# generator3.net
KiCad netlist of a schematic drawn in EAGLE
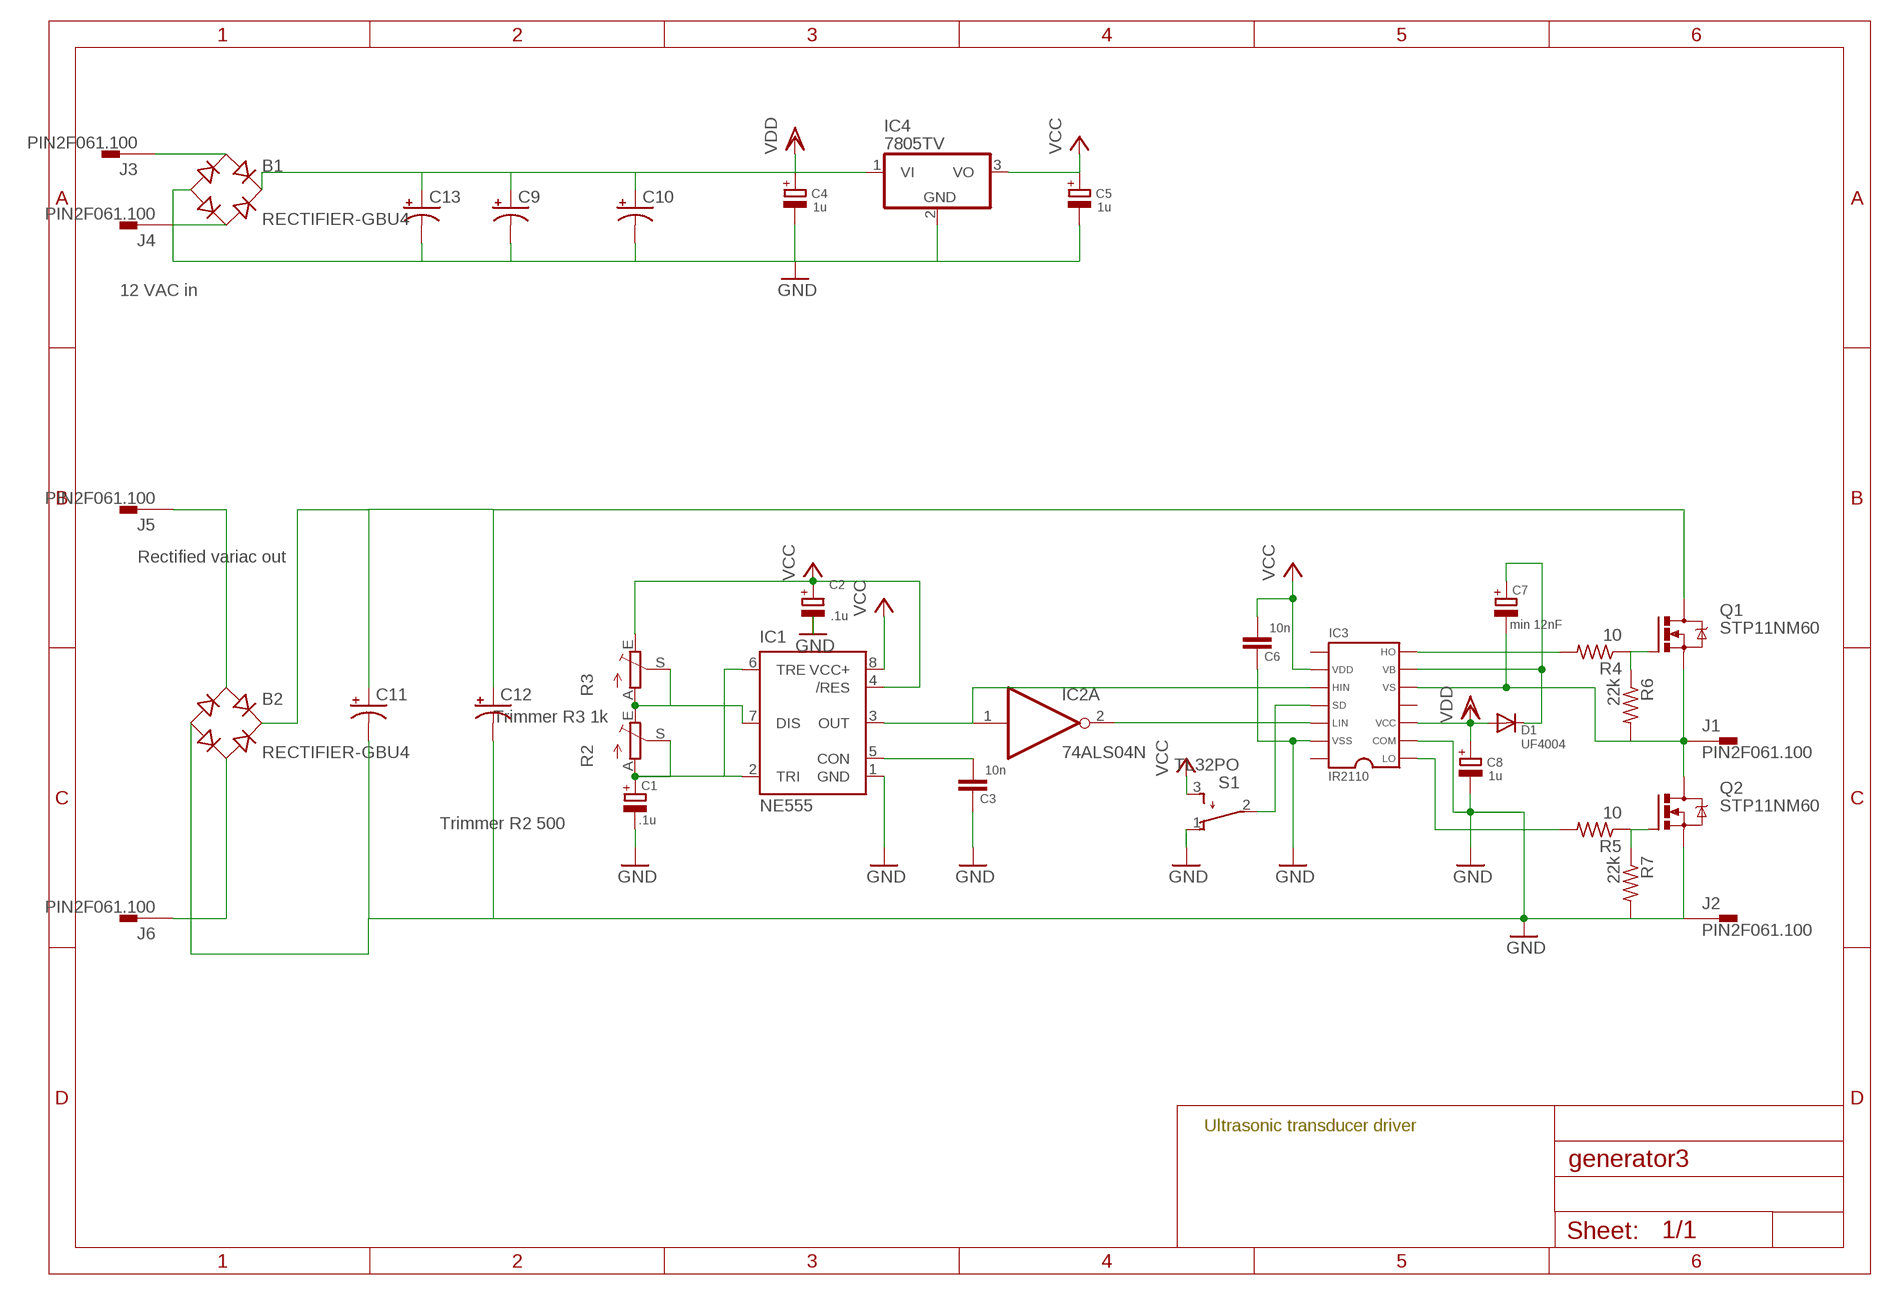
[diagram p0: schematic, sheet 1]

(export (version "E")
  (design (tool "Eeschema 10.0.6"))
  (components
    (comp (ref "B1")
      (value "RECTIFIER-GBU4")
      (footprint "eagle-import:GBU4")
      (libsource (lib "eagle-import") (part "RECTIFIER-GBU4"))
    )
    (comp (ref "B2")
      (value "RECTIFIER-GBU4")
      (footprint "eagle-import:GBU4")
      (libsource (lib "eagle-import") (part "RECTIFIER-GBU4"))
    )
    (comp (ref "C1")
      (value ".1u")
      (footprint "eagle-import:E5-8,5")
      (libsource (lib "eagle-import") (part "CPOL-EUE5-8.5"))
    )
    (comp (ref "C2")
      (value ".1u")
      (footprint "eagle-import:E5-8,5")
      (libsource (lib "eagle-import") (part "CPOL-EUE5-8.5"))
    )
    (comp (ref "C3")
      (value "10n")
      (footprint "eagle-import:C075-052X106")
      (libsource (lib "eagle-import") (part "C-EU075-052X106"))
    )
    (comp (ref "C4")
      (value "1u")
      (footprint "eagle-import:E5-8,5")
      (libsource (lib "eagle-import") (part "CPOL-EUE5-8.5"))
    )
    (comp (ref "C5")
      (value "1u")
      (footprint "eagle-import:E5-8,5")
      (libsource (lib "eagle-import") (part "CPOL-EUE5-8.5"))
    )
    (comp (ref "C6")
      (value "10n")
      (footprint "eagle-import:C075-052X106")
      (libsource (lib "eagle-import") (part "C-EU075-052X106"))
    )
    (comp (ref "C7")
      (value "min 12nF")
      (footprint "eagle-import:E5-8,5")
      (libsource (lib "eagle-import") (part "CPOL-EUE5-8.5"))
    )
    (comp (ref "C8")
      (value "1u")
      (footprint "eagle-import:E5-8,5")
      (libsource (lib "eagle-import") (part "CPOL-EUE5-8.5"))
    )
    (comp (ref "C9")
      (value "CPOL-USE7.5-18")
      (footprint "eagle-import:E7,5-18")
      (libsource (lib "eagle-import") (part "CPOL-USE7.5-18"))
    )
    (comp (ref "C10")
      (value "CPOL-USE7.5-18")
      (footprint "eagle-import:E7,5-18")
      (libsource (lib "eagle-import") (part "CPOL-USE7.5-18"))
    )
    (comp (ref "C11")
      (value "CPOL-USE10-35")
      (footprint "eagle-import:EB35D")
      (libsource (lib "eagle-import") (part "CPOL-USE10-35"))
    )
    (comp (ref "C12")
      (value "CPOL-USE10-35")
      (footprint "eagle-import:EB35D")
      (libsource (lib "eagle-import") (part "CPOL-USE10-35"))
    )
    (comp (ref "C13")
      (value "CPOL-USE7.5-18")
      (footprint "eagle-import:E7,5-18")
      (libsource (lib "eagle-import") (part "CPOL-USE7.5-18"))
    )
    (comp (ref "D1")
      (value "UF4004")
      (footprint "eagle-import:D-7.5")
      (libsource (lib "eagle-import") (part "DIODE-D-7.5"))
    )
    (comp (ref "IC1")
      (value "NE555")
      (footprint "eagle-import:DIL-08")
      (fields (field (name "MF") "Arrow Electronics") (field (name "MPN") "NE555N"))
      (libsource (lib "eagle-import") (part "NE555"))
    )
    (comp (ref "IC2")
      (value "74ALS04N")
      (footprint "eagle-import:DIL14")
      (libsource (lib "eagle-import") (part "7404NALS"))
    )
    (comp (ref "IC3")
      (value "IR2110")
      (footprint "eagle-import:DIL14")
      (libsource (lib "eagle-import") (part "IR2110"))
    )
    (comp (ref "IC4")
      (value "7805TV")
      (footprint "eagle-import:TO220V")
      (libsource (lib "eagle-import") (part "78TV05"))
    )
    (comp (ref "J1")
      (value "PIN2F061.100")
      (footprint "eagle-import:F061.100")
      (libsource (lib "eagle-import") (part "PIN2F061.100"))
    )
    (comp (ref "J2")
      (value "PIN2F061.100")
      (footprint "eagle-import:F061.100")
      (libsource (lib "eagle-import") (part "PIN2F061.100"))
    )
    (comp (ref "J3")
      (value "PIN2F061.100")
      (footprint "eagle-import:F061.100")
      (libsource (lib "eagle-import") (part "PIN2F061.100"))
    )
    (comp (ref "J4")
      (value "PIN2F061.100")
      (footprint "eagle-import:F061.100")
      (libsource (lib "eagle-import") (part "PIN2F061.100"))
    )
    (comp (ref "J5")
      (value "PIN2F061.100")
      (footprint "eagle-import:F061.100")
      (libsource (lib "eagle-import") (part "PIN2F061.100"))
    )
    (comp (ref "J6")
      (value "PIN2F061.100")
      (footprint "eagle-import:F061.100")
      (libsource (lib "eagle-import") (part "PIN2F061.100"))
    )
    (comp (ref "Q1")
      (value "STP11NM60")
      (footprint "eagle-import:TO220BV")
      (libsource (lib "eagle-import") (part "IRF530"))
    )
    (comp (ref "Q2")
      (value "STP11NM60")
      (footprint "eagle-import:TO220BV")
      (libsource (lib "eagle-import") (part "IRF530"))
    )
    (comp (ref "R2")
      (value "TRIM_EU-LI10")
      (footprint "eagle-import:LI10")
      (libsource (lib "eagle-import") (part "TRIM_EU-LI10"))
    )
    (comp (ref "R3")
      (value "TRIM_EU-LI10")
      (footprint "eagle-import:LI10")
      (libsource (lib "eagle-import") (part "TRIM_EU-LI10"))
    )
    (comp (ref "R4")
      (value "10")
      (footprint "eagle-import:0207_10")
      (libsource (lib "eagle-import") (part "R-US_0207/10"))
    )
    (comp (ref "R5")
      (value "10")
      (footprint "eagle-import:0207_10")
      (libsource (lib "eagle-import") (part "R-US_0207/10"))
    )
    (comp (ref "R6")
      (value "22k")
      (footprint "eagle-import:0207_10")
      (libsource (lib "eagle-import") (part "R-US_0207/10"))
    )
    (comp (ref "R7")
      (value "22k")
      (footprint "eagle-import:0207_10")
      (libsource (lib "eagle-import") (part "R-US_0207/10"))
    )
    (comp (ref "S1")
      (value "TL32PO")
      (footprint "eagle-import:TL3XPO")
      (libsource (lib "eagle-import") (part "TL32PO"))
    )
  )
  (nets
    (net (code "1") (name "GND") (class "Default")
      (node (ref "B1") (pin "-") (pinfunction "-_-") (pintype "passive"))
      (node (ref "B2") (pin "-") (pinfunction "-_-") (pintype "passive"))
      (node (ref "C1") (pin "-") (pinfunction "-_-") (pintype "passive"))
      (node (ref "C10") (pin "-") (pinfunction "-_-") (pintype "passive"))
      (node (ref "C11") (pin "-") (pinfunction "-_-") (pintype "passive"))
      (node (ref "C12") (pin "-") (pinfunction "-_-") (pintype "passive"))
      (node (ref "C13") (pin "-") (pinfunction "-_-") (pintype "passive"))
      (node (ref "C2") (pin "-") (pinfunction "-_-") (pintype "passive"))
      (node (ref "C3") (pin "1") (pinfunction "1_1") (pintype "passive"))
      (node (ref "C4") (pin "-") (pinfunction "-_-") (pintype "passive"))
      (node (ref "C5") (pin "-") (pinfunction "-_-") (pintype "passive"))
      (node (ref "C6") (pin "1") (pinfunction "1_1") (pintype "passive"))
      (node (ref "C8") (pin "-") (pinfunction "-_-") (pintype "passive"))
      (node (ref "C9") (pin "-") (pinfunction "-_-") (pintype "passive"))
      (node (ref "IC1") (pin "1") (pinfunction "GND_1") (pintype "power_in"))
      (node (ref "IC3") (pin "13") (pinfunction "13_13") (pintype "passive"))
      (node (ref "IC3") (pin "2") (pinfunction "2_2") (pintype "passive"))
      (node (ref "IC4") (pin "2") (pinfunction "GND_2") (pintype "passive"))
      (node (ref "J2") (pin "A1") (pinfunction "1_A1") (pintype "passive"))
      (node (ref "J2") (pin "A2") (pinfunction "1_A2") (pintype "passive"))
      (node (ref "Q2") (pin "S") (pinfunction "S_S") (pintype "passive"))
      (node (ref "R7") (pin "2") (pinfunction "2_2") (pintype "passive"))
      (node (ref "S1") (pin "1") (pinfunction "O_1") (pintype "passive"))
    )
    (net (code "2") (name "Net-(B1-PadAC1)") (class "Default")
      (node (ref "B1") (pin "AC1") (pinfunction "AC1_AC1") (pintype "passive"))
      (node (ref "J3") (pin "A1") (pinfunction "1_A1") (pintype "passive"))
      (node (ref "J3") (pin "A2") (pinfunction "1_A2") (pintype "passive"))
    )
    (net (code "3") (name "Net-(B1-PadAC2)") (class "Default")
      (node (ref "B1") (pin "AC2") (pinfunction "AC2_AC2") (pintype "passive"))
      (node (ref "J4") (pin "A1") (pinfunction "1_A1") (pintype "passive"))
      (node (ref "J4") (pin "A2") (pinfunction "1_A2") (pintype "passive"))
    )
    (net (code "4") (name "Net-(B2-Pad+)") (class "Default")
      (node (ref "B2") (pin "+") (pinfunction "+_+") (pintype "passive"))
      (node (ref "C11") (pin "+") (pinfunction "+_+") (pintype "passive"))
      (node (ref "C12") (pin "+") (pinfunction "+_+") (pintype "passive"))
      (node (ref "Q1") (pin "D") (pinfunction "D_D") (pintype "passive"))
    )
    (net (code "5") (name "Net-(B2-PadAC1)") (class "Default")
      (node (ref "B2") (pin "AC1") (pinfunction "AC1_AC1") (pintype "passive"))
      (node (ref "J5") (pin "A1") (pinfunction "1_A1") (pintype "passive"))
      (node (ref "J5") (pin "A2") (pinfunction "1_A2") (pintype "passive"))
    )
    (net (code "6") (name "Net-(B2-PadAC2)") (class "Default")
      (node (ref "B2") (pin "AC2") (pinfunction "AC2_AC2") (pintype "passive"))
      (node (ref "J6") (pin "A1") (pinfunction "1_A1") (pintype "passive"))
      (node (ref "J6") (pin "A2") (pinfunction "1_A2") (pintype "passive"))
    )
    (net (code "7") (name "Net-(C7-Pad+)") (class "Default")
      (node (ref "C7") (pin "+") (pinfunction "+_+") (pintype "passive"))
      (node (ref "D1") (pin "C") (pinfunction "C_C") (pintype "passive"))
      (node (ref "IC3") (pin "6") (pinfunction "6_6") (pintype "passive"))
    )
    (net (code "8") (name "Net-(C7-Pad-)") (class "Default")
      (node (ref "C7") (pin "-") (pinfunction "-_-") (pintype "passive"))
      (node (ref "IC3") (pin "5") (pinfunction "5_5") (pintype "passive"))
      (node (ref "J1") (pin "A1") (pinfunction "1_A1") (pintype "passive"))
      (node (ref "J1") (pin "A2") (pinfunction "1_A2") (pintype "passive"))
      (node (ref "Q1") (pin "S") (pinfunction "S_S") (pintype "passive"))
      (node (ref "Q2") (pin "D") (pinfunction "D_D") (pintype "passive"))
      (node (ref "R6") (pin "2") (pinfunction "2_2") (pintype "passive"))
    )
    (net (code "9") (name "Net-(IC1-CON)") (class "Default")
      (node (ref "C3") (pin "2") (pinfunction "2_2") (pintype "passive"))
      (node (ref "IC1") (pin "5") (pinfunction "CON_5") (pintype "input"))
    )
    (net (code "10") (name "Net-(IC1-DIS)") (class "Default")
      (node (ref "IC1") (pin "7") (pinfunction "DIS_7") (pintype "input"))
      (node (ref "R2") (pin "E") (pinfunction "E_E") (pintype "passive"))
      (node (ref "R3") (pin "A") (pinfunction "A_A") (pintype "passive"))
      (node (ref "R3") (pin "S") (pinfunction "S_S") (pintype "passive"))
    )
    (net (code "11") (name "Net-(IC1-OUT)") (class "Default")
      (node (ref "IC1") (pin "3") (pinfunction "OUT_3") (pintype "output"))
      (node (ref "IC2") (pin "1") (pinfunction "I_1") (pintype "input"))
      (node (ref "IC3") (pin "10") (pinfunction "10_10") (pintype "passive"))
    )
    (net (code "12") (name "Net-(IC1-TRE)") (class "Default")
      (node (ref "C1") (pin "+") (pinfunction "+_+") (pintype "passive"))
      (node (ref "IC1") (pin "2") (pinfunction "TRI_2") (pintype "input"))
      (node (ref "IC1") (pin "6") (pinfunction "TRE_6") (pintype "input"))
      (node (ref "R2") (pin "A") (pinfunction "A_A") (pintype "passive"))
      (node (ref "R2") (pin "S") (pinfunction "S_S") (pintype "passive"))
    )
    (net (code "13") (name "Net-(IC2A-O)") (class "Default")
      (node (ref "IC2") (pin "2") (pinfunction "O_2") (pintype "output"))
      (node (ref "IC3") (pin "12") (pinfunction "12_12") (pintype "passive"))
    )
    (net (code "14") (name "Net-(IC3-Pad1)") (class "Default")
      (node (ref "IC3") (pin "1") (pinfunction "1_1") (pintype "passive"))
      (node (ref "R5") (pin "2") (pinfunction "2_2") (pintype "passive"))
    )
    (net (code "15") (name "Net-(IC3-Pad7)") (class "Default")
      (node (ref "IC3") (pin "7") (pinfunction "7_7") (pintype "passive"))
      (node (ref "R4") (pin "2") (pinfunction "2_2") (pintype "passive"))
    )
    (net (code "16") (name "Net-(Q1-PadG)") (class "Default")
      (node (ref "Q1") (pin "G") (pinfunction "G_G") (pintype "passive"))
      (node (ref "R4") (pin "1") (pinfunction "1_1") (pintype "passive"))
      (node (ref "R6") (pin "1") (pinfunction "1_1") (pintype "passive"))
    )
    (net (code "17") (name "Net-(Q2-PadG)") (class "Default")
      (node (ref "Q2") (pin "G") (pinfunction "G_G") (pintype "passive"))
      (node (ref "R5") (pin "1") (pinfunction "1_1") (pintype "passive"))
      (node (ref "R7") (pin "1") (pinfunction "1_1") (pintype "passive"))
    )
    (net (code "18") (name "Net-(S1-P)") (class "Default")
      (node (ref "IC3") (pin "11") (pinfunction "11_11") (pintype "passive"))
      (node (ref "S1") (pin "2") (pinfunction "P_2") (pintype "passive"))
    )
    (net (code "19") (name "VCC") (class "Default")
      (node (ref "C2") (pin "+") (pinfunction "+_+") (pintype "passive"))
      (node (ref "C5") (pin "+") (pinfunction "+_+") (pintype "passive"))
      (node (ref "C6") (pin "2") (pinfunction "2_2") (pintype "passive"))
      (node (ref "IC1") (pin "4") (pinfunction "/RES_4") (pintype "input"))
      (node (ref "IC1") (pin "8") (pinfunction "VCC+_8") (pintype "power_in"))
      (node (ref "IC3") (pin "9") (pinfunction "9_9") (pintype "passive"))
      (node (ref "IC4") (pin "3") (pinfunction "VO_3") (pintype "passive"))
      (node (ref "R3") (pin "E") (pinfunction "E_E") (pintype "passive"))
      (node (ref "S1") (pin "3") (pinfunction "S_3") (pintype "passive"))
    )
    (net (code "20") (name "VDD") (class "Default")
      (node (ref "B1") (pin "+") (pinfunction "+_+") (pintype "passive"))
      (node (ref "C10") (pin "+") (pinfunction "+_+") (pintype "passive"))
      (node (ref "C13") (pin "+") (pinfunction "+_+") (pintype "passive"))
      (node (ref "C4") (pin "+") (pinfunction "+_+") (pintype "passive"))
      (node (ref "C8") (pin "+") (pinfunction "+_+") (pintype "passive"))
      (node (ref "C9") (pin "+") (pinfunction "+_+") (pintype "passive"))
      (node (ref "D1") (pin "A") (pinfunction "A_A") (pintype "passive"))
      (node (ref "IC3") (pin "3") (pinfunction "3_3") (pintype "passive"))
      (node (ref "IC4") (pin "1") (pinfunction "VI_1") (pintype "input"))
    )
    (net (code "21") (name "unconnected-(IC3-Pad4)") (class "Default")
      (node (ref "IC3") (pin "4") (pinfunction "4_4") (pintype "passive"))
    )
    (net (code "22") (name "unconnected-(IC3-Pad8)") (class "Default")
      (node (ref "IC3") (pin "8") (pinfunction "8_8") (pintype "passive"))
    )
    (net (code "23") (name "unconnected-(IC3-Pad14)") (class "Default")
      (node (ref "IC3") (pin "14") (pinfunction "14_14") (pintype "passive"))
    )
  )
)
